# Banks.net
KiCad netlist of a schematic drawn in Altium Designer
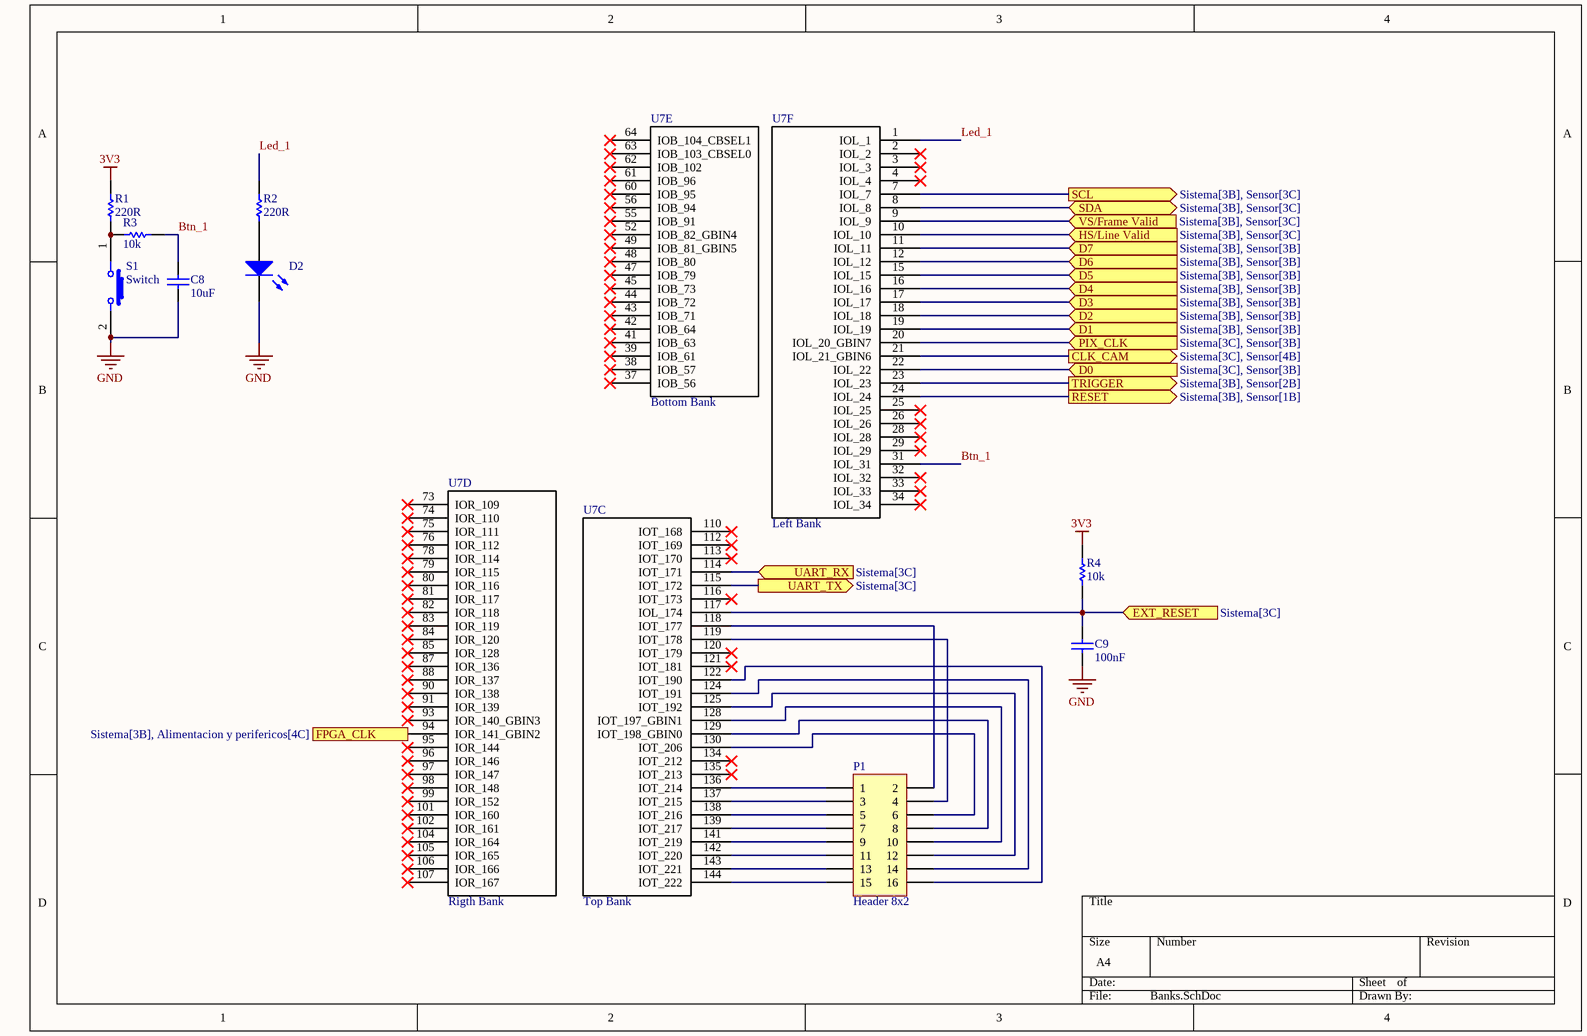
[diagram p0: Banks.SchDoc]

(export (version "E")
  (design (tool "Eeschema 10.0.6"))
  (components
    (comp (ref "C8")
      (value "10uF")
      (footprint "C_1206_3216_A")
      (description "Capacitor SMD 1206")
      (fields (field (name "TOLERANCE") "10%") (field (name "MANUFACTURER") "Samsung"))
      (libsource (lib "MyLibraryV2") (part "C_10uF_25V_c"))
    )
    (comp (ref "C9")
      (value "100nF")
      (footprint "C_0805_2013_b")
      (description "Capacitor SMD 0805")
      (fields (field (name "TOLERANCE") "10%") (field (name "VOLTAGE") "50V"))
      (libsource (lib "MyLibraryV2") (part "C_100nF_50V_b"))
    )
    (comp (ref "D2")
      (value "GREEN")
      (footprint "D_LED_0805_2013")
      (description "(Modificar) Diode SMD 0805")
      (libsource (lib "MyLibraryV2") (part "D_LED_SMD_0805"))
    )
    (comp (ref "P1")
      (value "Header 8x2")
      (footprint "P_HDR2X8_3D")
      (libsource (lib "MyLibraryV2") (part "P_Conector 8x2"))
    )
    (comp (ref "R1")
      (value "220R")
      (footprint "R_0805_2012_a")
      (description "Resistor SMD 0805")
      (fields (field (name "TOLERANCE") "1%") (field (name "MANUFACTURER") "Bourns"))
      (libsource (lib "MyLibraryV2") (part "R_220R_b"))
    )
    (comp (ref "R2")
      (value "220R")
      (footprint "R_0805_2012_a")
      (description "Resistor SMD 0805")
      (fields (field (name "TOLERANCE") "1%") (field (name "MANUFACTURER") "Bourns"))
      (libsource (lib "MyLibraryV2") (part "R_220R_b"))
    )
    (comp (ref "R3")
      (value "10k")
      (footprint "R_0805_2012_a")
      (description "Resistor SMD 0805")
      (fields (field (name "TOLERANCE") "1%") (field (name "MANUFACTURER") "Yageo"))
      (libsource (lib "MyLibraryV2") (part "R_10k_b"))
    )
    (comp (ref "R4")
      (value "10k")
      (footprint "R_0805_2012_a")
      (description "Resistor SMD 0805")
      (fields (field (name "TOLERANCE") "1%") (field (name "MANUFACTURER") "Yageo"))
      (libsource (lib "MyLibraryV2") (part "R_10k_b"))
    )
    (comp (ref "S1")
      (value "Switch")
      (footprint "S_SMD_SPST-NO")
      (description "(Generico) Switch SMD")
      (libsource (lib "MyLibraryV2") (part "S_?_3"))
    )
    (comp (ref "U7")
      (value "Top Bank")
      (footprint "U_TQFP-144")
      (libsource (lib "Mi_lib") (part "U_iCE40HX4K"))
    )
  )
  (nets
    (net (code "1") (name "/Btn_1") (class "Default")
      (node (ref "C8") (pin "2") (pinfunction "2_2") (pintype "passive"))
      (node (ref "R3") (pin "2") (pinfunction "2_2") (pintype "passive"))
      (node (ref "U7") (pin "31") (pinfunction "IOL_31_31") (pintype "passive"))
    )
    (net (code "2") (name "/CLK_CAM") (class "Default")
      (node (ref "U7") (pin "21") (pinfunction "IOL_21_GBIN6_21") (pintype "passive"))
    )
    (net (code "3") (name "/D0") (class "Default")
      (node (ref "U7") (pin "22") (pinfunction "IOL_22_22") (pintype "passive"))
    )
    (net (code "4") (name "/D1") (class "Default")
      (node (ref "U7") (pin "19") (pinfunction "IOL_19_19") (pintype "passive"))
    )
    (net (code "5") (name "/D2") (class "Default")
      (node (ref "U7") (pin "18") (pinfunction "IOL_18_18") (pintype "passive"))
    )
    (net (code "6") (name "/D3") (class "Default")
      (node (ref "U7") (pin "17") (pinfunction "IOL_17_17") (pintype "passive"))
    )
    (net (code "7") (name "/D4") (class "Default")
      (node (ref "U7") (pin "16") (pinfunction "IOL_16_16") (pintype "passive"))
    )
    (net (code "8") (name "/D5") (class "Default")
      (node (ref "U7") (pin "15") (pinfunction "IOL_15_15") (pintype "passive"))
    )
    (net (code "9") (name "/D6") (class "Default")
      (node (ref "U7") (pin "12") (pinfunction "IOL_12_12") (pintype "passive"))
    )
    (net (code "10") (name "/D7") (class "Default")
      (node (ref "U7") (pin "11") (pinfunction "IOL_11_11") (pintype "passive"))
    )
    (net (code "11") (name "/EXT_RESET") (class "Default")
      (node (ref "C9") (pin "2") (pinfunction "2_2") (pintype "passive"))
      (node (ref "R4") (pin "1") (pinfunction "1_1") (pintype "passive"))
      (node (ref "U7") (pin "117") (pinfunction "IOL_174_117") (pintype "passive"))
    )
    (net (code "12") (name "/FPGA_CLK") (class "Default")
      (node (ref "U7") (pin "94") (pinfunction "IOR_141_GBIN2_94") (pintype "passive"))
    )
    (net (code "13") (name "/HS{slash}Line Valid") (class "Default")
      (node (ref "U7") (pin "10") (pinfunction "IOL_10_10") (pintype "passive"))
    )
    (net (code "14") (name "/Led_1") (class "Default")
      (node (ref "R2") (pin "2") (pinfunction "2_2") (pintype "passive"))
      (node (ref "U7") (pin "1") (pinfunction "IOL_1_1") (pintype "passive"))
    )
    (net (code "15") (name "/PIX_CLK") (class "Default")
      (node (ref "U7") (pin "20") (pinfunction "IOL_20_GBIN7_20") (pintype "passive"))
    )
    (net (code "16") (name "/RESET") (class "Default")
      (node (ref "U7") (pin "24") (pinfunction "IOL_24_24") (pintype "passive"))
    )
    (net (code "17") (name "/SCL") (class "Default")
      (node (ref "U7") (pin "7") (pinfunction "IOL_7_7") (pintype "passive"))
    )
    (net (code "18") (name "/SDA") (class "Default")
      (node (ref "U7") (pin "8") (pinfunction "IOL_8_8") (pintype "passive"))
    )
    (net (code "19") (name "/TRIGGER") (class "Default")
      (node (ref "U7") (pin "23") (pinfunction "IOL_23_23") (pintype "passive"))
    )
    (net (code "20") (name "/UART_RX") (class "Default")
      (node (ref "U7") (pin "114") (pinfunction "IOT_171_114") (pintype "passive"))
    )
    (net (code "21") (name "/UART_TX") (class "Default")
      (node (ref "U7") (pin "115") (pinfunction "IOT_172_115") (pintype "passive"))
    )
    (net (code "22") (name "/VS{slash}Frame Valid") (class "Default")
      (node (ref "U7") (pin "9") (pinfunction "IOL_9_9") (pintype "passive"))
    )
    (net (code "23") (name "3V3") (class "Default")
      (node (ref "R1") (pin "2") (pinfunction "2_2") (pintype "passive"))
      (node (ref "R4") (pin "2") (pinfunction "2_2") (pintype "passive"))
    )
    (net (code "24") (name "GND") (class "Default")
      (node (ref "C8") (pin "1") (pinfunction "1_1") (pintype "passive"))
      (node (ref "C9") (pin "1") (pinfunction "1_1") (pintype "passive"))
      (node (ref "D2") (pin "1") (pinfunction "K_1") (pintype "passive"))
      (node (ref "S1") (pin "2") (pinfunction "2_2") (pintype "passive"))
    )
    (net (code "25") (name "Net-(D2-A)") (class "Default")
      (node (ref "D2") (pin "2") (pinfunction "A_2") (pintype "passive"))
      (node (ref "R2") (pin "1") (pinfunction "1_1") (pintype "passive"))
    )
    (net (code "26") (name "Net-(R1-Pad1)") (class "Default")
      (node (ref "R1") (pin "1") (pinfunction "1_1") (pintype "passive"))
      (node (ref "R3") (pin "1") (pinfunction "1_1") (pintype "passive"))
      (node (ref "S1") (pin "1") (pinfunction "1_1") (pintype "passive"))
    )
    (net (code "27") (name "Net-(U7C-IOT_177)") (class "Default")
      (node (ref "P1") (pin "2") (pinfunction "2_2") (pintype "passive"))
      (node (ref "U7") (pin "118") (pinfunction "IOT_177_118") (pintype "passive"))
    )
    (net (code "28") (name "Net-(U7C-IOT_178)") (class "Default")
      (node (ref "P1") (pin "4") (pinfunction "4_4") (pintype "passive"))
      (node (ref "U7") (pin "119") (pinfunction "IOT_178_119") (pintype "passive"))
    )
    (net (code "29") (name "Net-(U7C-IOT_190)") (class "Default")
      (node (ref "P1") (pin "16") (pinfunction "16_16") (pintype "passive"))
      (node (ref "U7") (pin "122") (pinfunction "IOT_190_122") (pintype "passive"))
    )
    (net (code "30") (name "Net-(U7C-IOT_191)") (class "Default")
      (node (ref "P1") (pin "14") (pinfunction "14_14") (pintype "passive"))
      (node (ref "U7") (pin "124") (pinfunction "IOT_191_124") (pintype "passive"))
    )
    (net (code "31") (name "Net-(U7C-IOT_192)") (class "Default")
      (node (ref "P1") (pin "12") (pinfunction "12_12") (pintype "passive"))
      (node (ref "U7") (pin "125") (pinfunction "IOT_192_125") (pintype "passive"))
    )
    (net (code "32") (name "Net-(U7C-IOT_197_GBIN1)") (class "Default")
      (node (ref "P1") (pin "10") (pinfunction "10_10") (pintype "passive"))
      (node (ref "U7") (pin "128") (pinfunction "IOT_197_GBIN1_128") (pintype "passive"))
    )
    (net (code "33") (name "Net-(U7C-IOT_198_GBIN0)") (class "Default")
      (node (ref "P1") (pin "8") (pinfunction "8_8") (pintype "passive"))
      (node (ref "U7") (pin "129") (pinfunction "IOT_198_GBIN0_129") (pintype "passive"))
    )
    (net (code "34") (name "Net-(U7C-IOT_206)") (class "Default")
      (node (ref "P1") (pin "6") (pinfunction "6_6") (pintype "passive"))
      (node (ref "U7") (pin "130") (pinfunction "IOT_206_130") (pintype "passive"))
    )
    (net (code "35") (name "Net-(U7C-IOT_214)") (class "Default")
      (node (ref "P1") (pin "1") (pinfunction "1_1") (pintype "passive"))
      (node (ref "U7") (pin "136") (pinfunction "IOT_214_136") (pintype "passive"))
    )
    (net (code "36") (name "Net-(U7C-IOT_215)") (class "Default")
      (node (ref "P1") (pin "3") (pinfunction "3_3") (pintype "passive"))
      (node (ref "U7") (pin "137") (pinfunction "IOT_215_137") (pintype "passive"))
    )
    (net (code "37") (name "Net-(U7C-IOT_216)") (class "Default")
      (node (ref "P1") (pin "5") (pinfunction "5_5") (pintype "passive"))
      (node (ref "U7") (pin "138") (pinfunction "IOT_216_138") (pintype "passive"))
    )
    (net (code "38") (name "Net-(U7C-IOT_217)") (class "Default")
      (node (ref "P1") (pin "7") (pinfunction "7_7") (pintype "passive"))
      (node (ref "U7") (pin "139") (pinfunction "IOT_217_139") (pintype "passive"))
    )
    (net (code "39") (name "Net-(U7C-IOT_219)") (class "Default")
      (node (ref "P1") (pin "9") (pinfunction "9_9") (pintype "passive"))
      (node (ref "U7") (pin "141") (pinfunction "IOT_219_141") (pintype "passive"))
    )
    (net (code "40") (name "Net-(U7C-IOT_220)") (class "Default")
      (node (ref "P1") (pin "11") (pinfunction "11_11") (pintype "passive"))
      (node (ref "U7") (pin "142") (pinfunction "IOT_220_142") (pintype "passive"))
    )
    (net (code "41") (name "Net-(U7C-IOT_221)") (class "Default")
      (node (ref "P1") (pin "13") (pinfunction "13_13") (pintype "passive"))
      (node (ref "U7") (pin "143") (pinfunction "IOT_221_143") (pintype "passive"))
    )
    (net (code "42") (name "Net-(U7C-IOT_222)") (class "Default")
      (node (ref "P1") (pin "15") (pinfunction "15_15") (pintype "passive"))
      (node (ref "U7") (pin "144") (pinfunction "IOT_222_144") (pintype "passive"))
    )
    (net (code "43") (name "unconnected-(U7C-IOT_168-Pad110)") (class "Default")
      (node (ref "U7") (pin "110") (pinfunction "IOT_168_110") (pintype "passive+no_connect"))
    )
    (net (code "44") (name "unconnected-(U7C-IOT_169-Pad112)") (class "Default")
      (node (ref "U7") (pin "112") (pinfunction "IOT_169_112") (pintype "passive+no_connect"))
    )
    (net (code "45") (name "unconnected-(U7C-IOT_170-Pad113)") (class "Default")
      (node (ref "U7") (pin "113") (pinfunction "IOT_170_113") (pintype "passive+no_connect"))
    )
    (net (code "46") (name "unconnected-(U7C-IOT_173-Pad116)") (class "Default")
      (node (ref "U7") (pin "116") (pinfunction "IOT_173_116") (pintype "passive+no_connect"))
    )
    (net (code "47") (name "unconnected-(U7C-IOT_179-Pad120)") (class "Default")
      (node (ref "U7") (pin "120") (pinfunction "IOT_179_120") (pintype "passive+no_connect"))
    )
    (net (code "48") (name "unconnected-(U7C-IOT_181-Pad121)") (class "Default")
      (node (ref "U7") (pin "121") (pinfunction "IOT_181_121") (pintype "passive+no_connect"))
    )
    (net (code "49") (name "unconnected-(U7C-IOT_212-Pad134)") (class "Default")
      (node (ref "U7") (pin "134") (pinfunction "IOT_212_134") (pintype "passive+no_connect"))
    )
    (net (code "50") (name "unconnected-(U7C-IOT_213-Pad135)") (class "Default")
      (node (ref "U7") (pin "135") (pinfunction "IOT_213_135") (pintype "passive+no_connect"))
    )
    (net (code "51") (name "unconnected-(U7D-IOR_109-Pad73)") (class "Default")
      (node (ref "U7") (pin "73") (pinfunction "IOR_109_73") (pintype "passive+no_connect"))
    )
    (net (code "52") (name "unconnected-(U7D-IOR_110-Pad74)") (class "Default")
      (node (ref "U7") (pin "74") (pinfunction "IOR_110_74") (pintype "passive+no_connect"))
    )
    (net (code "53") (name "unconnected-(U7D-IOR_111-Pad75)") (class "Default")
      (node (ref "U7") (pin "75") (pinfunction "IOR_111_75") (pintype "passive+no_connect"))
    )
    (net (code "54") (name "unconnected-(U7D-IOR_112-Pad76)") (class "Default")
      (node (ref "U7") (pin "76") (pinfunction "IOR_112_76") (pintype "passive+no_connect"))
    )
    (net (code "55") (name "unconnected-(U7D-IOR_114-Pad78)") (class "Default")
      (node (ref "U7") (pin "78") (pinfunction "IOR_114_78") (pintype "passive+no_connect"))
    )
    (net (code "56") (name "unconnected-(U7D-IOR_115-Pad79)") (class "Default")
      (node (ref "U7") (pin "79") (pinfunction "IOR_115_79") (pintype "passive+no_connect"))
    )
    (net (code "57") (name "unconnected-(U7D-IOR_116-Pad80)") (class "Default")
      (node (ref "U7") (pin "80") (pinfunction "IOR_116_80") (pintype "passive+no_connect"))
    )
    (net (code "58") (name "unconnected-(U7D-IOR_117-Pad81)") (class "Default")
      (node (ref "U7") (pin "81") (pinfunction "IOR_117_81") (pintype "passive+no_connect"))
    )
    (net (code "59") (name "unconnected-(U7D-IOR_118-Pad82)") (class "Default")
      (node (ref "U7") (pin "82") (pinfunction "IOR_118_82") (pintype "passive+no_connect"))
    )
    (net (code "60") (name "unconnected-(U7D-IOR_119-Pad83)") (class "Default")
      (node (ref "U7") (pin "83") (pinfunction "IOR_119_83") (pintype "passive+no_connect"))
    )
    (net (code "61") (name "unconnected-(U7D-IOR_120-Pad84)") (class "Default")
      (node (ref "U7") (pin "84") (pinfunction "IOR_120_84") (pintype "passive+no_connect"))
    )
    (net (code "62") (name "unconnected-(U7D-IOR_128-Pad85)") (class "Default")
      (node (ref "U7") (pin "85") (pinfunction "IOR_128_85") (pintype "passive+no_connect"))
    )
    (net (code "63") (name "unconnected-(U7D-IOR_136-Pad87)") (class "Default")
      (node (ref "U7") (pin "87") (pinfunction "IOR_136_87") (pintype "passive+no_connect"))
    )
    (net (code "64") (name "unconnected-(U7D-IOR_137-Pad88)") (class "Default")
      (node (ref "U7") (pin "88") (pinfunction "IOR_137_88") (pintype "passive+no_connect"))
    )
    (net (code "65") (name "unconnected-(U7D-IOR_138-Pad90)") (class "Default")
      (node (ref "U7") (pin "90") (pinfunction "IOR_138_90") (pintype "passive+no_connect"))
    )
    (net (code "66") (name "unconnected-(U7D-IOR_139-Pad91)") (class "Default")
      (node (ref "U7") (pin "91") (pinfunction "IOR_139_91") (pintype "passive+no_connect"))
    )
    (net (code "67") (name "unconnected-(U7D-IOR_140_GBIN3-Pad93)") (class "Default")
      (node (ref "U7") (pin "93") (pinfunction "IOR_140_GBIN3_93") (pintype "passive+no_connect"))
    )
    (net (code "68") (name "unconnected-(U7D-IOR_144-Pad95)") (class "Default")
      (node (ref "U7") (pin "95") (pinfunction "IOR_144_95") (pintype "passive+no_connect"))
    )
    (net (code "69") (name "unconnected-(U7D-IOR_146-Pad96)") (class "Default")
      (node (ref "U7") (pin "96") (pinfunction "IOR_146_96") (pintype "passive+no_connect"))
    )
    (net (code "70") (name "unconnected-(U7D-IOR_147-Pad97)") (class "Default")
      (node (ref "U7") (pin "97") (pinfunction "IOR_147_97") (pintype "passive+no_connect"))
    )
    (net (code "71") (name "unconnected-(U7D-IOR_148-Pad98)") (class "Default")
      (node (ref "U7") (pin "98") (pinfunction "IOR_148_98") (pintype "passive+no_connect"))
    )
    (net (code "72") (name "unconnected-(U7D-IOR_152-Pad99)") (class "Default")
      (node (ref "U7") (pin "99") (pinfunction "IOR_152_99") (pintype "passive+no_connect"))
    )
    (net (code "73") (name "unconnected-(U7D-IOR_160-Pad101)") (class "Default")
      (node (ref "U7") (pin "101") (pinfunction "IOR_160_101") (pintype "passive+no_connect"))
    )
    (net (code "74") (name "unconnected-(U7D-IOR_161-Pad102)") (class "Default")
      (node (ref "U7") (pin "102") (pinfunction "IOR_161_102") (pintype "passive+no_connect"))
    )
    (net (code "75") (name "unconnected-(U7D-IOR_164-Pad104)") (class "Default")
      (node (ref "U7") (pin "104") (pinfunction "IOR_164_104") (pintype "passive+no_connect"))
    )
    (net (code "76") (name "unconnected-(U7D-IOR_165-Pad105)") (class "Default")
      (node (ref "U7") (pin "105") (pinfunction "IOR_165_105") (pintype "passive+no_connect"))
    )
    (net (code "77") (name "unconnected-(U7D-IOR_166-Pad106)") (class "Default")
      (node (ref "U7") (pin "106") (pinfunction "IOR_166_106") (pintype "passive+no_connect"))
    )
    (net (code "78") (name "unconnected-(U7D-IOR_167-Pad107)") (class "Default")
      (node (ref "U7") (pin "107") (pinfunction "IOR_167_107") (pintype "passive+no_connect"))
    )
    (net (code "79") (name "unconnected-(U7E-IOB_56-Pad37)") (class "Default")
      (node (ref "U7") (pin "37") (pinfunction "IOB_56_37") (pintype "passive+no_connect"))
    )
    (net (code "80") (name "unconnected-(U7E-IOB_57-Pad38)") (class "Default")
      (node (ref "U7") (pin "38") (pinfunction "IOB_57_38") (pintype "passive+no_connect"))
    )
    (net (code "81") (name "unconnected-(U7E-IOB_61-Pad39)") (class "Default")
      (node (ref "U7") (pin "39") (pinfunction "IOB_61_39") (pintype "passive+no_connect"))
    )
    (net (code "82") (name "unconnected-(U7E-IOB_63-Pad41)") (class "Default")
      (node (ref "U7") (pin "41") (pinfunction "IOB_63_41") (pintype "passive+no_connect"))
    )
    (net (code "83") (name "unconnected-(U7E-IOB_64-Pad42)") (class "Default")
      (node (ref "U7") (pin "42") (pinfunction "IOB_64_42") (pintype "passive+no_connect"))
    )
    (net (code "84") (name "unconnected-(U7E-IOB_71-Pad43)") (class "Default")
      (node (ref "U7") (pin "43") (pinfunction "IOB_71_43") (pintype "passive+no_connect"))
    )
    (net (code "85") (name "unconnected-(U7E-IOB_72-Pad44)") (class "Default")
      (node (ref "U7") (pin "44") (pinfunction "IOB_72_44") (pintype "passive+no_connect"))
    )
    (net (code "86") (name "unconnected-(U7E-IOB_73-Pad45)") (class "Default")
      (node (ref "U7") (pin "45") (pinfunction "IOB_73_45") (pintype "passive+no_connect"))
    )
    (net (code "87") (name "unconnected-(U7E-IOB_79-Pad47)") (class "Default")
      (node (ref "U7") (pin "47") (pinfunction "IOB_79_47") (pintype "passive+no_connect"))
    )
    (net (code "88") (name "unconnected-(U7E-IOB_80-Pad48)") (class "Default")
      (node (ref "U7") (pin "48") (pinfunction "IOB_80_48") (pintype "passive+no_connect"))
    )
    (net (code "89") (name "unconnected-(U7E-IOB_81_GBIN5-Pad49)") (class "Default")
      (node (ref "U7") (pin "49") (pinfunction "IOB_81_GBIN5_49") (pintype "passive+no_connect"))
    )
    (net (code "90") (name "unconnected-(U7E-IOB_82_GBIN4-Pad52)") (class "Default")
      (node (ref "U7") (pin "52") (pinfunction "IOB_82_GBIN4_52") (pintype "passive+no_connect"))
    )
    (net (code "91") (name "unconnected-(U7E-IOB_91-Pad55)") (class "Default")
      (node (ref "U7") (pin "55") (pinfunction "IOB_91_55") (pintype "passive+no_connect"))
    )
    (net (code "92") (name "unconnected-(U7E-IOB_94-Pad56)") (class "Default")
      (node (ref "U7") (pin "56") (pinfunction "IOB_94_56") (pintype "passive+no_connect"))
    )
    (net (code "93") (name "unconnected-(U7E-IOB_95-Pad60)") (class "Default")
      (node (ref "U7") (pin "60") (pinfunction "IOB_95_60") (pintype "passive+no_connect"))
    )
    (net (code "94") (name "unconnected-(U7E-IOB_96-Pad61)") (class "Default")
      (node (ref "U7") (pin "61") (pinfunction "IOB_96_61") (pintype "passive+no_connect"))
    )
    (net (code "95") (name "unconnected-(U7E-IOB_102-Pad62)") (class "Default")
      (node (ref "U7") (pin "62") (pinfunction "IOB_102_62") (pintype "passive+no_connect"))
    )
    (net (code "96") (name "unconnected-(U7E-IOB_103_CBSEL0-Pad63)") (class "Default")
      (node (ref "U7") (pin "63") (pinfunction "IOB_103_CBSEL0_63") (pintype "passive+no_connect"))
    )
    (net (code "97") (name "unconnected-(U7E-IOB_104_CBSEL1-Pad64)") (class "Default")
      (node (ref "U7") (pin "64") (pinfunction "IOB_104_CBSEL1_64") (pintype "passive+no_connect"))
    )
    (net (code "98") (name "unconnected-(U7F-IOL_2-Pad2)") (class "Default")
      (node (ref "U7") (pin "2") (pinfunction "IOL_2_2") (pintype "passive+no_connect"))
    )
    (net (code "99") (name "unconnected-(U7F-IOL_3-Pad3)") (class "Default")
      (node (ref "U7") (pin "3") (pinfunction "IOL_3_3") (pintype "passive+no_connect"))
    )
    (net (code "100") (name "unconnected-(U7F-IOL_4-Pad4)") (class "Default")
      (node (ref "U7") (pin "4") (pinfunction "IOL_4_4") (pintype "passive+no_connect"))
    )
    (net (code "101") (name "unconnected-(U7F-IOL_25-Pad25)") (class "Default")
      (node (ref "U7") (pin "25") (pinfunction "IOL_25_25") (pintype "passive+no_connect"))
    )
    (net (code "102") (name "unconnected-(U7F-IOL_26-Pad26)") (class "Default")
      (node (ref "U7") (pin "26") (pinfunction "IOL_26_26") (pintype "passive+no_connect"))
    )
    (net (code "103") (name "unconnected-(U7F-IOL_28-Pad28)") (class "Default")
      (node (ref "U7") (pin "28") (pinfunction "IOL_28_28") (pintype "passive+no_connect"))
    )
    (net (code "104") (name "unconnected-(U7F-IOL_29-Pad29)") (class "Default")
      (node (ref "U7") (pin "29") (pinfunction "IOL_29_29") (pintype "passive+no_connect"))
    )
    (net (code "105") (name "unconnected-(U7F-IOL_32-Pad32)") (class "Default")
      (node (ref "U7") (pin "32") (pinfunction "IOL_32_32") (pintype "passive+no_connect"))
    )
    (net (code "106") (name "unconnected-(U7F-IOL_33-Pad33)") (class "Default")
      (node (ref "U7") (pin "33") (pinfunction "IOL_33_33") (pintype "passive+no_connect"))
    )
    (net (code "107") (name "unconnected-(U7F-IOL_34-Pad34)") (class "Default")
      (node (ref "U7") (pin "34") (pinfunction "IOL_34_34") (pintype "passive+no_connect"))
    )
  )
)
